# ESP-audio-breakout.net
KiCad netlist of a schematic drawn in Altium Designer
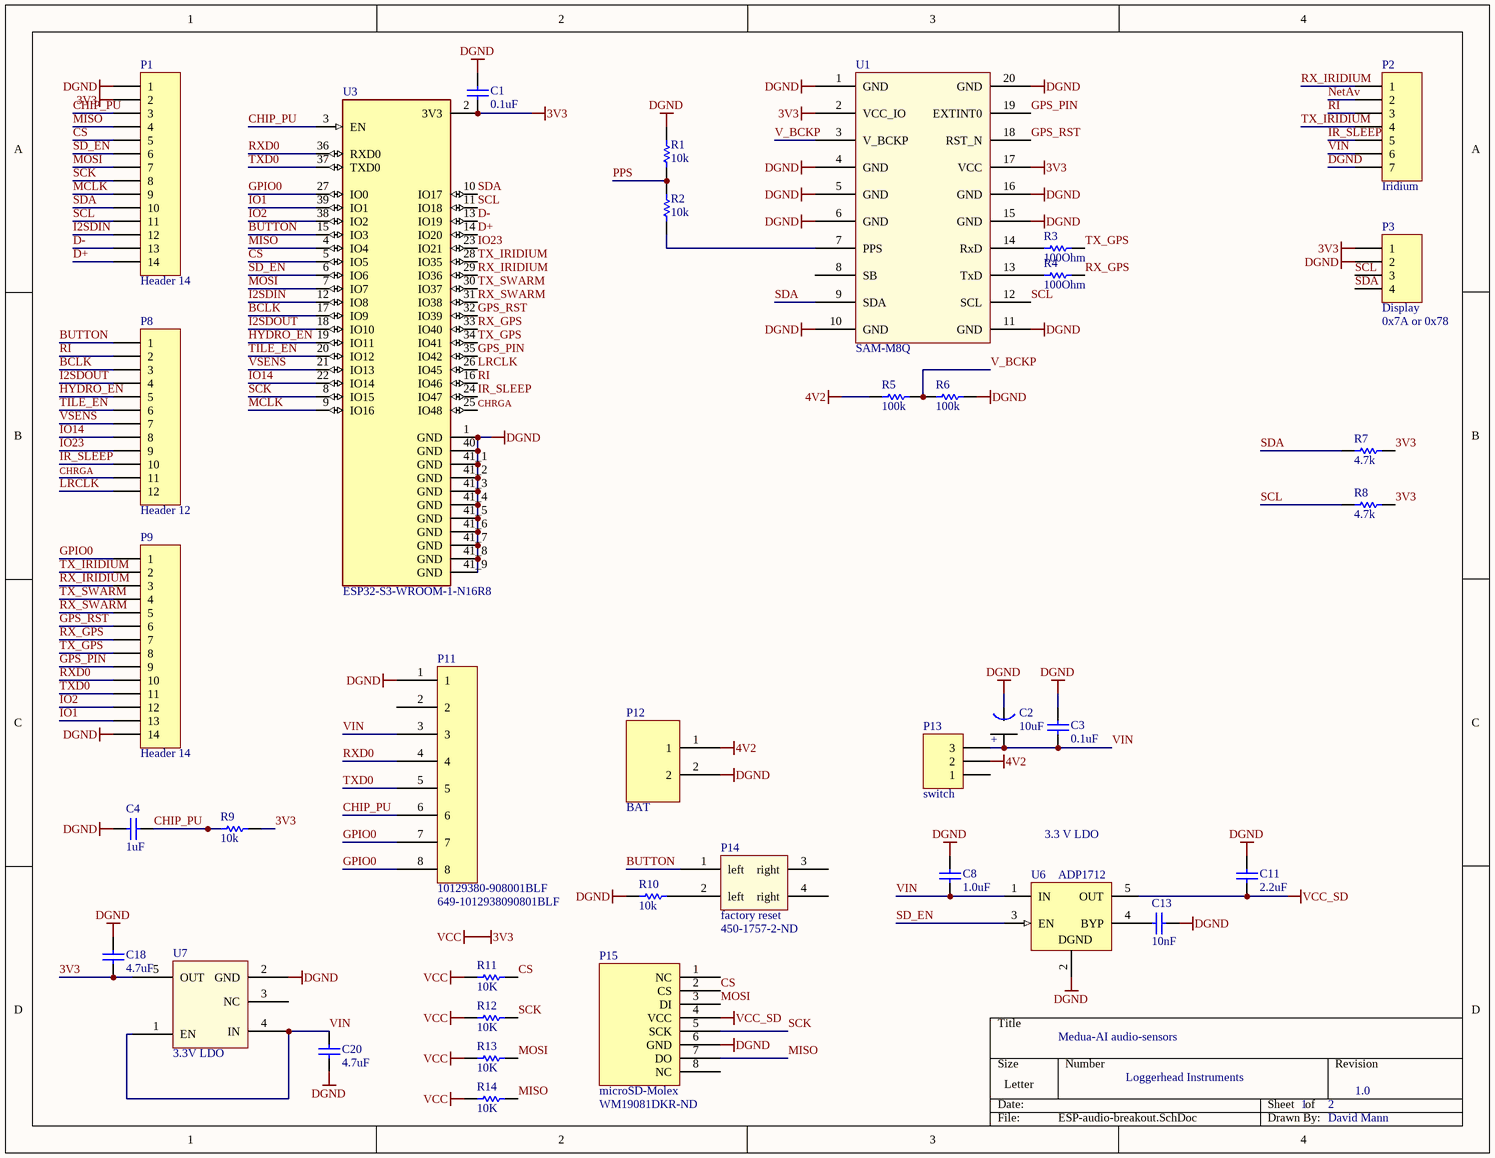
[diagram p0: ESP-audio-breakout.SchDoc]

(export (version "E")
  (design (tool "Eeschema 10.0.6"))
  (components
    (comp (ref "C1")
      (value "0.1uF")
      (footprint "0402")
      (description "Ceramic Chip Capacitor - Standard")
      (fields (field (name "PUBLISHER") "Altium Limited"))
      (libsource (lib "KEMET Chip Capacitor") (part "C0402"))
    )
    (comp (ref "C2") (value "10uF") (footprint "Tant0805") (libsource (lib "Loggerhead") (part "Tant0805")))
    (comp (ref "C3")
      (value "0.1uF")
      (footprint "0402")
      (description "Ceramic Chip Capacitor - Standard")
      (fields (field (name "PUBLISHER") "Altium Limited"))
      (libsource (lib "KEMET Chip Capacitor") (part "C0402"))
    )
    (comp (ref "C4")
      (value "1uF")
      (footprint "0402")
      (description "Ceramic Chip Capacitor - Standard")
      (fields (field (name "PUBLISHER") "Altium Limited"))
      (libsource (lib "KEMET Chip Capacitor") (part "C0402"))
    )
    (comp (ref "C8")
      (value "1.0uF")
      (footprint "0402")
      (description "Ceramic Chip Capacitor - Standard")
      (fields (field (name "PUBLISHER") "Altium Limited"))
      (libsource (lib "KEMET Chip Capacitor") (part "C0402"))
    )
    (comp (ref "C11")
      (value "2.2uF")
      (footprint "0402")
      (description "Ceramic Chip Capacitor - Standard")
      (fields (field (name "PUBLISHER") "Altium Limited"))
      (libsource (lib "KEMET Chip Capacitor") (part "C0402"))
    )
    (comp (ref "C13")
      (value "10nF")
      (footprint "0402")
      (description "Ceramic Chip Capacitor - Standard")
      (fields (field (name "PUBLISHER") "Altium Limited"))
      (libsource (lib "KEMET Chip Capacitor") (part "C0402"))
    )
    (comp (ref "C18")
      (value "4.7uF")
      (footprint "0402")
      (description "Ceramic Chip Capacitor - Standard")
      (fields (field (name "PUBLISHER") "Altium Limited"))
      (libsource (lib "KEMET Chip Capacitor") (part "C0402"))
    )
    (comp (ref "C20")
      (value "4.7uF")
      (footprint "0402")
      (description "Ceramic Chip Capacitor - Standard")
      (fields (field (name "PUBLISHER") "Altium Limited"))
      (libsource (lib "KEMET Chip Capacitor") (part "C0402"))
    )
    (comp (ref "P1")
      (value "Header 14")
      (footprint "HDR1X14")
      (description "Header, 14-Pin")
      (fields (field (name "PUBLISHER") "Altium Limited"))
      (libsource (lib "Miscellaneous Connectors") (part "Header 14"))
    )
    (comp (ref "P2")
      (value "Iridium")
      (footprint "HDR1X7")
      (description "Header, 7-Pin")
      (fields (field (name "PUBLISHER") "Altium Limited"))
      (libsource (lib "Miscellaneous Connectors") (part "Header 7"))
    )
    (comp (ref "P3")
      (value "Display")
      (footprint "HDR1X4")
      (description "Header, 4-Pin")
      (fields (field (name "PUBLISHER") "Altium Limited"))
      (libsource (lib "Miscellaneous Connectors") (part "Header 4"))
    )
    (comp (ref "P8")
      (value "Header 12")
      (footprint "HDR1X12")
      (description "Header, 12-Pin")
      (fields (field (name "PUBLISHER") "Altium Limited"))
      (libsource (lib "Miscellaneous Connectors") (part "Header 12"))
    )
    (comp (ref "P9")
      (value "Header 14")
      (footprint "HDR1X14")
      (description "Header, 14-Pin")
      (fields (field (name "PUBLISHER") "Altium Limited"))
      (libsource (lib "Miscellaneous Connectors") (part "Header 14"))
    )
    (comp (ref "P11")
      (value "10129380-908001BLF")
      (footprint "Header_8_SMT")
      (description "Surface mount header")
      (fields (field (name "SUPPLIER PART NUMBER 1") "649-1012938090801BLF"))
      (libsource (lib "Loggerhead") (part "Header8_SMT"))
    )
    (comp (ref "P12")
      (value "BAT")
      (footprint "HDR_2x1_2mm")
      (libsource (lib "Loggerhead") (part "HDR_2x1_2mm"))
    )
    (comp (ref "P13")
      (value "switch")
      (footprint "HDR1X3")
      (description "Header, 3-Pin")
      (fields (field (name "PUBLISHER") "Altium Limited"))
      (libsource (lib "Miscellaneous Connectors") (part "Header 3"))
    )
    (comp (ref "P14")
      (value "factory reset")
      (footprint "SOP4")
      (fields (field (name "SUPPLIER PART NUMBER 1") "450-1757-2-ND"))
      (libsource (lib "Loggerhead") (part "pushbutton"))
    )
    (comp (ref "P15")
      (value "microSD-Molex")
      (footprint "microSD_Molex_hinged")
      (fields (field (name "SUPPLIER PART NUMBER 1") "WM19081DKR-ND"))
      (libsource (lib "Loggerhead") (part "microSD_Molex_hinged"))
    )
    (comp (ref "R1")
      (value "10k")
      (footprint "3-0603")
      (fields (field (name "PUBLISHER") "Altium Limited"))
      (libsource (lib "Panasonic Resistor") (part "ERJ3RK"))
    )
    (comp (ref "R2")
      (value "10k")
      (footprint "3-0603")
      (fields (field (name "PUBLISHER") "Altium Limited"))
      (libsource (lib "Panasonic Resistor") (part "ERJ3RK"))
    )
    (comp (ref "R3")
      (value "100Ohm")
      (footprint "2-0402")
      (fields (field (name "PUBLISHER") "Altium Limited"))
      (libsource (lib "Panasonic Resistor") (part "ERJ2RB"))
    )
    (comp (ref "R4")
      (value "100Ohm")
      (footprint "2-0402")
      (fields (field (name "PUBLISHER") "Altium Limited"))
      (libsource (lib "Panasonic Resistor") (part "ERJ2RB"))
    )
    (comp (ref "R5")
      (value "100k")
      (footprint "3-0603")
      (fields (field (name "PUBLISHER") "Altium Limited"))
      (libsource (lib "Panasonic Resistor") (part "ERJ3RK"))
    )
    (comp (ref "R6")
      (value "100k")
      (footprint "3-0603")
      (fields (field (name "PUBLISHER") "Altium Limited"))
      (libsource (lib "Panasonic Resistor") (part "ERJ3RK"))
    )
    (comp (ref "R7")
      (value "4.7k")
      (footprint "3-0603")
      (fields (field (name "PUBLISHER") "Altium Limited"))
      (libsource (lib "Panasonic Resistor") (part "ERJ3RK"))
    )
    (comp (ref "R8")
      (value "4.7k")
      (footprint "3-0603")
      (fields (field (name "PUBLISHER") "Altium Limited"))
      (libsource (lib "Panasonic Resistor") (part "ERJ3RK"))
    )
    (comp (ref "R9")
      (value "10k")
      (footprint "2-0402")
      (fields (field (name "PUBLISHER") "Altium Limited"))
      (libsource (lib "Panasonic Resistor") (part "ERJ2RB"))
    )
    (comp (ref "R10")
      (value "10k")
      (footprint "2-0402")
      (fields (field (name "PUBLISHER") "Altium Limited"))
      (libsource (lib "Panasonic Resistor") (part "ERJ2RB"))
    )
    (comp (ref "R11")
      (value "10K")
      (footprint "3-0603")
      (fields (field (name "PUBLISHER") "Altium Limited"))
      (libsource (lib "Panasonic Resistor") (part "ERJ3EK"))
    )
    (comp (ref "R12")
      (value "10K")
      (footprint "3-0603")
      (fields (field (name "PUBLISHER") "Altium Limited"))
      (libsource (lib "Panasonic Resistor") (part "ERJ3EK"))
    )
    (comp (ref "R13")
      (value "10K")
      (footprint "3-0603")
      (fields (field (name "PUBLISHER") "Altium Limited"))
      (libsource (lib "Panasonic Resistor") (part "ERJ3EK"))
    )
    (comp (ref "R14")
      (value "10K")
      (footprint "3-0603")
      (fields (field (name "PUBLISHER") "Altium Limited"))
      (libsource (lib "Panasonic Resistor") (part "ERJ3EK"))
    )
    (comp (ref "U1")
      (value "SAM-M8Q")
      (footprint "GPS SAM-MQ8")
      (libsource (lib "Loggerhead") (part "GPS SAM-M8Q"))
    )
    (comp (ref "U3")
      (value "ESP32-S3-WROOM-1-N16R8")
      (footprint "XCVR_ESP32-S3-WROOM-1-N16R2")
      (description "Bluetooth, WiFi 802.11b/g/n, Bluetooth v5.0 Transceiver Module 2.4GHz PCB Trace Surface Mount")
      (fields (field (name "MP") "ESP32-S3-WROOM-1-N16R2") (field (name "MF") "Espressif Systems"))
      (libsource (lib "ESP32-S3-WROOM-1-N16R2") (part "ESP32-S3-WROOM-1-N16R2"))
    )
    (comp (ref "U6")
      (value "ADP1712")
      (footprint "MF05A_N")
      (description "Micropower, 150mA Low-Noise Ultra Low-Dropout CMOS Voltage Regulator")
      (fields
        (field (name "PARTNUMBER") "LP3985IM5-3.3")
        (field (name "MANUFACTURER") "National Semiconductor")
        (field (name "PUBLISHER") "Altium Limited")
      )
      (libsource (lib "NSC LDO") (part "LP3985IM5-3.3"))
    )
    (comp (ref "U7")
      (value "3.3V LDO")
      (footprint "AP7361C-33Y5-13")
      (libsource (lib "Loggerhead") (part "AP7361C-33Y5-13"))
    )
  )
  (nets
    (net (code "1") (name "/BCLK") (class "Default")
      (node (ref "P8") (pin "3") (pinfunction "3_3") (pintype "passive"))
      (node (ref "U3") (pin "17") (pinfunction "IO9_17") (pintype "bidirectional"))
    )
    (net (code "2") (name "/BUTTON") (class "Default")
      (node (ref "P14") (pin "1") (pinfunction "left_1") (pintype "passive"))
      (node (ref "P8") (pin "1") (pinfunction "1_1") (pintype "passive"))
      (node (ref "U3") (pin "15") (pinfunction "IO3_15") (pintype "bidirectional"))
    )
    (net (code "3") (name "/CHIP_PU") (class "Default")
      (node (ref "C4") (pin "1") (pinfunction "1_1") (pintype "passive"))
      (node (ref "P1") (pin "3") (pinfunction "3_3") (pintype "passive"))
      (node (ref "P11") (pin "6") (pinfunction "6_6") (pintype "passive"))
      (node (ref "R9") (pin "2") (pinfunction "2_2") (pintype "passive"))
      (node (ref "U3") (pin "3") (pinfunction "EN_3") (pintype "input"))
    )
    (net (code "4") (name "/CHRGA") (class "Default")
      (node (ref "P8") (pin "11") (pinfunction "11_11") (pintype "passive"))
      (node (ref "U3") (pin "25") (pinfunction "IO48_25") (pintype "bidirectional"))
    )
    (net (code "5") (name "/CS") (class "Default")
      (node (ref "P1") (pin "5") (pinfunction "5_5") (pintype "passive"))
      (node (ref "P15") (pin "2") (pinfunction "CS_2") (pintype "passive"))
      (node (ref "R11") (pin "2") (pinfunction "2_2") (pintype "passive"))
      (node (ref "U3") (pin "5") (pinfunction "IO5_5") (pintype "bidirectional"))
    )
    (net (code "6") (name "/D+") (class "Default")
      (node (ref "P1") (pin "14") (pinfunction "14_14") (pintype "passive"))
      (node (ref "U3") (pin "14") (pinfunction "IO20_14") (pintype "bidirectional"))
    )
    (net (code "7") (name "/D-") (class "Default")
      (node (ref "P1") (pin "13") (pinfunction "13_13") (pintype "passive"))
      (node (ref "U3") (pin "13") (pinfunction "IO19_13") (pintype "bidirectional"))
    )
    (net (code "8") (name "/GPIO0") (class "Default")
      (node (ref "P11") (pin "7") (pinfunction "7_7") (pintype "passive"))
      (node (ref "P11") (pin "8") (pinfunction "8_8") (pintype "passive"))
      (node (ref "P9") (pin "1") (pinfunction "1_1") (pintype "passive"))
      (node (ref "U3") (pin "27") (pinfunction "IO0_27") (pintype "bidirectional"))
    )
    (net (code "9") (name "/GPS_PIN") (class "Default")
      (node (ref "P9") (pin "9") (pinfunction "9_9") (pintype "passive"))
      (node (ref "U1") (pin "19") (pinfunction "EXTINT0_19") (pintype "passive"))
      (node (ref "U3") (pin "35") (pinfunction "IO42_35") (pintype "bidirectional"))
    )
    (net (code "10") (name "/GPS_RST") (class "Default")
      (node (ref "P9") (pin "6") (pinfunction "6_6") (pintype "passive"))
      (node (ref "U1") (pin "18") (pinfunction "RST_N_18") (pintype "passive"))
      (node (ref "U3") (pin "32") (pinfunction "IO39_32") (pintype "bidirectional"))
    )
    (net (code "11") (name "/HYDRO_EN") (class "Default")
      (node (ref "P8") (pin "5") (pinfunction "5_5") (pintype "passive"))
      (node (ref "U3") (pin "19") (pinfunction "IO11_19") (pintype "bidirectional"))
    )
    (net (code "12") (name "/I2SDIN") (class "Default")
      (node (ref "P1") (pin "12") (pinfunction "12_12") (pintype "passive"))
      (node (ref "U3") (pin "12") (pinfunction "IO8_12") (pintype "bidirectional"))
    )
    (net (code "13") (name "/I2SDOUT") (class "Default")
      (node (ref "P8") (pin "4") (pinfunction "4_4") (pintype "passive"))
      (node (ref "U3") (pin "18") (pinfunction "IO10_18") (pintype "bidirectional"))
    )
    (net (code "14") (name "/IO1") (class "Default")
      (node (ref "P9") (pin "13") (pinfunction "13_13") (pintype "passive"))
      (node (ref "U3") (pin "39") (pinfunction "IO1_39") (pintype "bidirectional"))
    )
    (net (code "15") (name "/IO2") (class "Default")
      (node (ref "P9") (pin "12") (pinfunction "12_12") (pintype "passive"))
      (node (ref "U3") (pin "38") (pinfunction "IO2_38") (pintype "bidirectional"))
    )
    (net (code "16") (name "/IO14") (class "Default")
      (node (ref "P8") (pin "8") (pinfunction "8_8") (pintype "passive"))
      (node (ref "U3") (pin "22") (pinfunction "IO14_22") (pintype "bidirectional"))
    )
    (net (code "17") (name "/IO23") (class "Default")
      (node (ref "P8") (pin "9") (pinfunction "9_9") (pintype "passive"))
      (node (ref "U3") (pin "23") (pinfunction "IO21_23") (pintype "bidirectional"))
    )
    (net (code "18") (name "/IR_SLEEP") (class "Default")
      (node (ref "P2") (pin "5") (pinfunction "5_5") (pintype "passive"))
      (node (ref "P8") (pin "10") (pinfunction "10_10") (pintype "passive"))
      (node (ref "U3") (pin "24") (pinfunction "IO47_24") (pintype "bidirectional"))
    )
    (net (code "19") (name "/LRCLK") (class "Default")
      (node (ref "P8") (pin "12") (pinfunction "12_12") (pintype "passive"))
      (node (ref "U3") (pin "26") (pinfunction "IO45_26") (pintype "bidirectional"))
    )
    (net (code "20") (name "/MCLK") (class "Default")
      (node (ref "P1") (pin "9") (pinfunction "9_9") (pintype "passive"))
      (node (ref "U3") (pin "9") (pinfunction "IO16_9") (pintype "bidirectional"))
    )
    (net (code "21") (name "/MISO") (class "Default")
      (node (ref "P1") (pin "4") (pinfunction "4_4") (pintype "passive"))
      (node (ref "P15") (pin "7") (pinfunction "DO_7") (pintype "passive"))
      (node (ref "R14") (pin "2") (pinfunction "2_2") (pintype "passive"))
      (node (ref "U3") (pin "4") (pinfunction "IO4_4") (pintype "bidirectional"))
    )
    (net (code "22") (name "/MOSI") (class "Default")
      (node (ref "P1") (pin "7") (pinfunction "7_7") (pintype "passive"))
      (node (ref "P15") (pin "3") (pinfunction "DI_3") (pintype "passive"))
      (node (ref "R13") (pin "2") (pinfunction "2_2") (pintype "passive"))
      (node (ref "U3") (pin "7") (pinfunction "IO7_7") (pintype "bidirectional"))
    )
    (net (code "23") (name "/NetAv") (class "Default")
      (node (ref "P2") (pin "2") (pinfunction "2_2") (pintype "passive"))
    )
    (net (code "24") (name "/PPS") (class "Default")
      (node (ref "R1") (pin "2") (pinfunction "2_2") (pintype "passive"))
      (node (ref "R2") (pin "1") (pinfunction "1_1") (pintype "passive"))
    )
    (net (code "25") (name "/RI") (class "Default")
      (node (ref "P2") (pin "3") (pinfunction "3_3") (pintype "passive"))
      (node (ref "P8") (pin "2") (pinfunction "2_2") (pintype "passive"))
      (node (ref "U3") (pin "16") (pinfunction "IO46_16") (pintype "bidirectional"))
    )
    (net (code "26") (name "/RXD0") (class "Default")
      (node (ref "P11") (pin "4") (pinfunction "4_4") (pintype "passive"))
      (node (ref "P9") (pin "10") (pinfunction "10_10") (pintype "passive"))
      (node (ref "U3") (pin "36") (pinfunction "RXD0_36") (pintype "bidirectional"))
    )
    (net (code "27") (name "/RX_GPS") (class "Default")
      (node (ref "P9") (pin "7") (pinfunction "7_7") (pintype "passive"))
      (node (ref "R4") (pin "1") (pinfunction "1_1") (pintype "passive"))
      (node (ref "U3") (pin "33") (pinfunction "IO40_33") (pintype "bidirectional"))
    )
    (net (code "28") (name "/RX_IRIDIUM") (class "Default")
      (node (ref "P2") (pin "1") (pinfunction "1_1") (pintype "passive"))
      (node (ref "P9") (pin "3") (pinfunction "3_3") (pintype "passive"))
      (node (ref "U3") (pin "29") (pinfunction "IO36_29") (pintype "bidirectional"))
    )
    (net (code "29") (name "/RX_SWARM") (class "Default")
      (node (ref "P9") (pin "5") (pinfunction "5_5") (pintype "passive"))
      (node (ref "U3") (pin "31") (pinfunction "IO38_31") (pintype "bidirectional"))
    )
    (net (code "30") (name "/SCK") (class "Default")
      (node (ref "P1") (pin "8") (pinfunction "8_8") (pintype "passive"))
      (node (ref "P15") (pin "5") (pinfunction "SCK_5") (pintype "passive"))
      (node (ref "R12") (pin "2") (pinfunction "2_2") (pintype "passive"))
      (node (ref "U3") (pin "8") (pinfunction "IO15_8") (pintype "bidirectional"))
    )
    (net (code "31") (name "/SCL") (class "Default")
      (node (ref "P1") (pin "11") (pinfunction "11_11") (pintype "passive"))
      (node (ref "P3") (pin "3") (pinfunction "3_3") (pintype "passive"))
      (node (ref "R8") (pin "1") (pinfunction "1_1") (pintype "passive"))
      (node (ref "U1") (pin "12") (pinfunction "SCL_12") (pintype "passive"))
      (node (ref "U3") (pin "11") (pinfunction "IO18_11") (pintype "bidirectional"))
    )
    (net (code "32") (name "/SDA") (class "Default")
      (node (ref "P1") (pin "10") (pinfunction "10_10") (pintype "passive"))
      (node (ref "P3") (pin "4") (pinfunction "4_4") (pintype "passive"))
      (node (ref "R7") (pin "1") (pinfunction "1_1") (pintype "passive"))
      (node (ref "U1") (pin "9") (pinfunction "SDA_9") (pintype "passive"))
      (node (ref "U3") (pin "10") (pinfunction "IO17_10") (pintype "bidirectional"))
    )
    (net (code "33") (name "/SD_EN") (class "Default")
      (node (ref "P1") (pin "6") (pinfunction "6_6") (pintype "passive"))
      (node (ref "U3") (pin "6") (pinfunction "IO6_6") (pintype "bidirectional"))
      (node (ref "U6") (pin "3") (pinfunction "EN_3") (pintype "input"))
    )
    (net (code "34") (name "/TILE_EN") (class "Default")
      (node (ref "P8") (pin "6") (pinfunction "6_6") (pintype "passive"))
      (node (ref "U3") (pin "20") (pinfunction "IO12_20") (pintype "bidirectional"))
    )
    (net (code "35") (name "/TXD0") (class "Default")
      (node (ref "P11") (pin "5") (pinfunction "5_5") (pintype "passive"))
      (node (ref "P9") (pin "11") (pinfunction "11_11") (pintype "passive"))
      (node (ref "U3") (pin "37") (pinfunction "TXD0_37") (pintype "bidirectional"))
    )
    (net (code "36") (name "/TX_GPS") (class "Default")
      (node (ref "P9") (pin "8") (pinfunction "8_8") (pintype "passive"))
      (node (ref "R3") (pin "1") (pinfunction "1_1") (pintype "passive"))
      (node (ref "U3") (pin "34") (pinfunction "IO41_34") (pintype "bidirectional"))
    )
    (net (code "37") (name "/TX_IRIDIUM") (class "Default")
      (node (ref "P2") (pin "4") (pinfunction "4_4") (pintype "passive"))
      (node (ref "P9") (pin "2") (pinfunction "2_2") (pintype "passive"))
      (node (ref "U3") (pin "28") (pinfunction "IO35_28") (pintype "bidirectional"))
    )
    (net (code "38") (name "/TX_SWARM") (class "Default")
      (node (ref "P9") (pin "4") (pinfunction "4_4") (pintype "passive"))
      (node (ref "U3") (pin "30") (pinfunction "IO37_30") (pintype "bidirectional"))
    )
    (net (code "39") (name "/VIN") (class "Default")
      (node (ref "C2") (pin "2") (pinfunction "+_2") (pintype "passive"))
      (node (ref "C20") (pin "1") (pinfunction "1_1") (pintype "passive"))
      (node (ref "C3") (pin "1") (pinfunction "1_1") (pintype "passive"))
      (node (ref "C8") (pin "1") (pinfunction "1_1") (pintype "passive"))
      (node (ref "P11") (pin "3") (pinfunction "3_3") (pintype "passive"))
      (node (ref "P13") (pin "3") (pinfunction "3_3") (pintype "passive"))
      (node (ref "P2") (pin "6") (pinfunction "6_6") (pintype "passive"))
      (node (ref "U6") (pin "1") (pinfunction "IN_1") (pintype "power_in"))
      (node (ref "U7") (pin "1") (pinfunction "EN_1") (pintype "passive"))
      (node (ref "U7") (pin "4") (pinfunction "IN_4") (pintype "passive"))
    )
    (net (code "40") (name "/VSENS") (class "Default")
      (node (ref "P8") (pin "7") (pinfunction "7_7") (pintype "passive"))
      (node (ref "U3") (pin "21") (pinfunction "IO13_21") (pintype "bidirectional"))
    )
    (net (code "41") (name "/V_BCKP") (class "Default")
      (node (ref "R5") (pin "1") (pinfunction "1_1") (pintype "passive"))
      (node (ref "R6") (pin "2") (pinfunction "2_2") (pintype "passive"))
      (node (ref "U1") (pin "3") (pinfunction "V_BCKP_3") (pintype "passive"))
    )
    (net (code "42") (name "3V3") (class "Default")
      (node (ref "C1") (pin "1") (pinfunction "1_1") (pintype "passive"))
      (node (ref "C18") (pin "2") (pinfunction "2_2") (pintype "passive"))
      (node (ref "P1") (pin "2") (pinfunction "2_2") (pintype "passive"))
      (node (ref "P3") (pin "1") (pinfunction "1_1") (pintype "passive"))
      (node (ref "R11") (pin "1") (pinfunction "1_1") (pintype "passive"))
      (node (ref "R12") (pin "1") (pinfunction "1_1") (pintype "passive"))
      (node (ref "R13") (pin "1") (pinfunction "1_1") (pintype "passive"))
      (node (ref "R14") (pin "1") (pinfunction "1_1") (pintype "passive"))
      (node (ref "R7") (pin "2") (pinfunction "2_2") (pintype "passive"))
      (node (ref "R8") (pin "2") (pinfunction "2_2") (pintype "passive"))
      (node (ref "R9") (pin "1") (pinfunction "1_1") (pintype "passive"))
      (node (ref "U1") (pin "17") (pinfunction "VCC_17") (pintype "passive"))
      (node (ref "U1") (pin "2") (pinfunction "VCC_IO_2") (pintype "passive"))
      (node (ref "U3") (pin "2") (pinfunction "3V3_2") (pintype "power_in"))
      (node (ref "U7") (pin "5") (pinfunction "OUT_5") (pintype "passive"))
    )
    (net (code "43") (name "4V2") (class "Default")
      (node (ref "P12") (pin "1") (pinfunction "1_1") (pintype "passive"))
      (node (ref "P13") (pin "2") (pinfunction "2_2") (pintype "passive"))
      (node (ref "R5") (pin "2") (pinfunction "2_2") (pintype "passive"))
    )
    (net (code "44") (name "DGND") (class "Default")
      (node (ref "C1") (pin "2") (pinfunction "2_2") (pintype "passive"))
      (node (ref "C11") (pin "2") (pinfunction "2_2") (pintype "passive"))
      (node (ref "C13") (pin "1") (pinfunction "1_1") (pintype "passive"))
      (node (ref "C18") (pin "1") (pinfunction "1_1") (pintype "passive"))
      (node (ref "C2") (pin "1") (pinfunction "GND_1") (pintype "passive"))
      (node (ref "C20") (pin "2") (pinfunction "2_2") (pintype "passive"))
      (node (ref "C3") (pin "2") (pinfunction "2_2") (pintype "passive"))
      (node (ref "C4") (pin "2") (pinfunction "2_2") (pintype "passive"))
      (node (ref "C8") (pin "2") (pinfunction "2_2") (pintype "passive"))
      (node (ref "P1") (pin "1") (pinfunction "1_1") (pintype "passive"))
      (node (ref "P11") (pin "1") (pinfunction "1_1") (pintype "passive"))
      (node (ref "P12") (pin "2") (pinfunction "2_2") (pintype "passive"))
      (node (ref "P15") (pin "6") (pinfunction "GND_6") (pintype "passive"))
      (node (ref "P2") (pin "7") (pinfunction "7_7") (pintype "passive"))
      (node (ref "P3") (pin "2") (pinfunction "2_2") (pintype "passive"))
      (node (ref "P9") (pin "14") (pinfunction "14_14") (pintype "passive"))
      (node (ref "R1") (pin "1") (pinfunction "1_1") (pintype "passive"))
      (node (ref "R10") (pin "2") (pinfunction "2_2") (pintype "passive"))
      (node (ref "R6") (pin "1") (pinfunction "1_1") (pintype "passive"))
      (node (ref "U1") (pin "1") (pinfunction "GND_1") (pintype "passive"))
      (node (ref "U1") (pin "10") (pinfunction "GND_10") (pintype "passive"))
      (node (ref "U1") (pin "11") (pinfunction "GND_11") (pintype "passive"))
      (node (ref "U1") (pin "15") (pinfunction "GND_15") (pintype "passive"))
      (node (ref "U1") (pin "16") (pinfunction "GND_16") (pintype "passive"))
      (node (ref "U1") (pin "20") (pinfunction "GND_20") (pintype "passive"))
      (node (ref "U1") (pin "4") (pinfunction "GND_4") (pintype "passive"))
      (node (ref "U1") (pin "5") (pinfunction "GND_5") (pintype "passive"))
      (node (ref "U1") (pin "6") (pinfunction "GND_6") (pintype "passive"))
      (node (ref "U3") (pin "1") (pinfunction "GND_1") (pintype "power_in"))
      (node (ref "U3") (pin "40") (pinfunction "GND_40") (pintype "power_in"))
      (node (ref "U3") (pin "41_1") (pinfunction "GND_41_1") (pintype "power_in"))
      (node (ref "U3") (pin "41_2") (pinfunction "GND_41_2") (pintype "power_in"))
      (node (ref "U3") (pin "41_3") (pinfunction "GND_41_3") (pintype "power_in"))
      (node (ref "U3") (pin "41_4") (pinfunction "GND_41_4") (pintype "power_in"))
      (node (ref "U3") (pin "41_5") (pinfunction "GND_41_5") (pintype "power_in"))
      (node (ref "U3") (pin "41_6") (pinfunction "GND_41_6") (pintype "power_in"))
      (node (ref "U3") (pin "41_7") (pinfunction "GND_41_7") (pintype "power_in"))
      (node (ref "U3") (pin "41_8") (pinfunction "GND_41_8") (pintype "power_in"))
      (node (ref "U3") (pin "41_9") (pinfunction "GND_41_9") (pintype "power_in"))
      (node (ref "U6") (pin "2") (pinfunction "GND_2") (pintype "power_in"))
      (node (ref "U7") (pin "2") (pinfunction "GND_2") (pintype "passive"))
    )
    (net (code "45") (name "Net-(P14-left-Pad2)") (class "Default")
      (node (ref "P14") (pin "2") (pinfunction "left_2") (pintype "passive"))
      (node (ref "R10") (pin "1") (pinfunction "1_1") (pintype "passive"))
    )
    (net (code "46") (name "Net-(U1-PPS)") (class "Default")
      (node (ref "R2") (pin "2") (pinfunction "2_2") (pintype "passive"))
      (node (ref "U1") (pin "7") (pinfunction "PPS_7") (pintype "passive"))
    )
    (net (code "47") (name "Net-(U1-RxD)") (class "Default")
      (node (ref "R3") (pin "2") (pinfunction "2_2") (pintype "passive"))
      (node (ref "U1") (pin "14") (pinfunction "RxD_14") (pintype "passive"))
    )
    (net (code "48") (name "Net-(U1-TxD)") (class "Default")
      (node (ref "R4") (pin "2") (pinfunction "2_2") (pintype "passive"))
      (node (ref "U1") (pin "13") (pinfunction "TxD_13") (pintype "passive"))
    )
    (net (code "49") (name "Net-(U6-BYP)") (class "Default")
      (node (ref "C13") (pin "2") (pinfunction "2_2") (pintype "passive"))
      (node (ref "U6") (pin "4") (pinfunction "BYP_4") (pintype "passive"))
    )
    (net (code "50") (name "VCC_SD") (class "Default")
      (node (ref "C11") (pin "1") (pinfunction "1_1") (pintype "passive"))
      (node (ref "P15") (pin "4") (pinfunction "VCC_4") (pintype "passive"))
      (node (ref "U6") (pin "5") (pinfunction "OUT_5") (pintype "power_in"))
    )
    (net (code "51") (name "unconnected-(P11-Pad2)") (class "Default")
      (node (ref "P11") (pin "2") (pinfunction "2_2") (pintype "passive"))
    )
    (net (code "52") (name "unconnected-(P13-Pad1)") (class "Default")
      (node (ref "P13") (pin "1") (pinfunction "1_1") (pintype "passive"))
    )
    (net (code "53") (name "unconnected-(P14-right-Pad3)") (class "Default")
      (node (ref "P14") (pin "3") (pinfunction "right_3") (pintype "passive"))
    )
    (net (code "54") (name "unconnected-(P14-right-Pad4)") (class "Default")
      (node (ref "P14") (pin "4") (pinfunction "right_4") (pintype "passive"))
    )
    (net (code "55") (name "unconnected-(P15-NC-Pad1)") (class "Default")
      (node (ref "P15") (pin "1") (pinfunction "NC_1") (pintype "passive"))
    )
    (net (code "56") (name "unconnected-(P15-NC-Pad8)") (class "Default")
      (node (ref "P15") (pin "8") (pinfunction "NC_8") (pintype "passive"))
    )
    (net (code "57") (name "unconnected-(U1-SB-Pad8)") (class "Default")
      (node (ref "U1") (pin "8") (pinfunction "SB_8") (pintype "passive"))
    )
    (net (code "58") (name "unconnected-(U7-NC-Pad3)") (class "Default")
      (node (ref "U7") (pin "3") (pinfunction "NC_3") (pintype "passive"))
    )
  )
)
